# Maker_Faire_Machine_Panel3.net
KiCad netlist of a schematic drawn in EAGLE
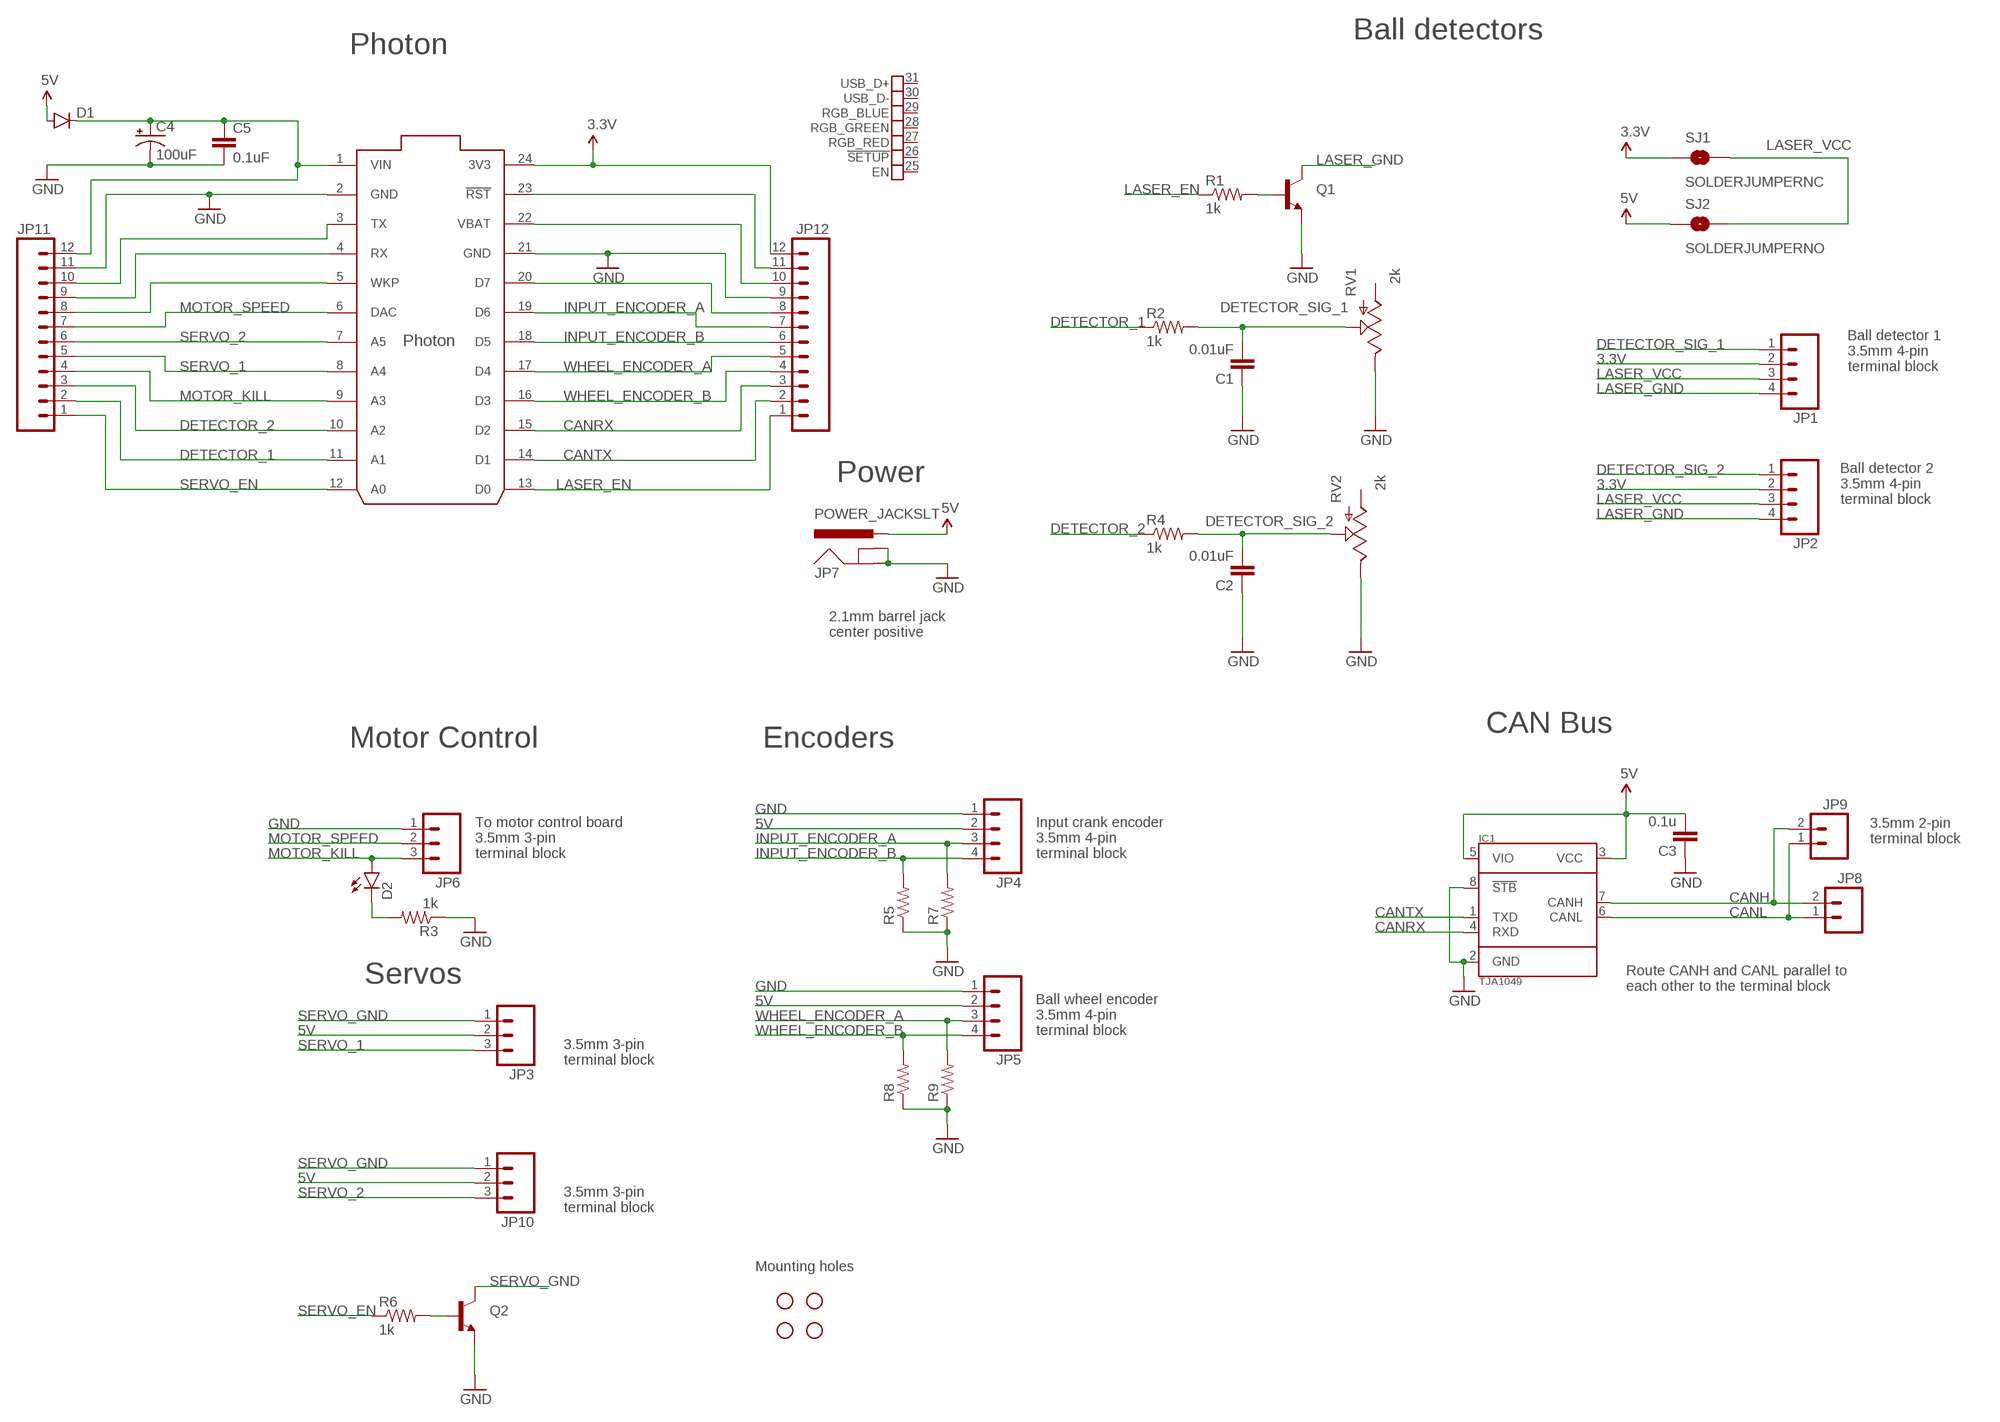
[diagram p0: schematic, sheet 1]

(export (version "E")
  (design (tool "Eeschema 10.0.6"))
  (components
    (comp (ref "C1")
      (value "0.01uF")
      (footprint "eagle-import:1206")
      (fields (field (name "PARTNO") "12065C103KAT2A"))
      (libsource (lib "eagle-import") (part "SparkFun-Passives_CAP1206"))
    )
    (comp (ref "C2")
      (value "0.01uF")
      (footprint "eagle-import:1206")
      (fields (field (name "PARTNO") "12065C103KAT2A"))
      (libsource (lib "eagle-import") (part "SparkFun-Passives_CAP1206"))
    )
    (comp (ref "C3")
      (value "0.1u")
      (footprint "eagle-import:1206")
      (fields (field (name "PARTNO") "12065C104KAT2A"))
      (libsource (lib "eagle-import") (part "CAP1206"))
    )
    (comp (ref "C4")
      (value "100uF")
      (footprint "eagle-import:CPOL-RADIAL-100UF-25V")
      (fields (field (name "PARTNO") "EEU-FM1H101B"))
      (libsource (lib "eagle-import") (part "CAP_POLPTH1"))
    )
    (comp (ref "C5")
      (value "0.1uF")
      (footprint "eagle-import:1206")
      (fields (field (name "PARTNO") "12065C104KAT2A"))
      (libsource (lib "eagle-import") (part "CAP1206"))
    )
    (comp (ref "D1")
      (value "DIODESMA")
      (footprint "eagle-import:SMA-DIODE")
      (fields (field (name "PARTNO") "B230A-13-F"))
      (libsource (lib "eagle-import") (part "DIODESMA"))
    )
    (comp (ref "D2")
      (value "LED5MM")
      (footprint "eagle-import:LED5MM")
      (fields (field (name "PARTNO") "SSL-LX5093HD"))
      (libsource (lib "eagle-import") (part "LED5MM"))
    )
    (comp (ref "IC1")
      (value "TJA1049")
      (footprint "eagle-import:SO8")
      (fields (field (name "PARTNO") "TJA1049T-118"))
      (libsource (lib "eagle-import") (part "TJA1049"))
    )
    (comp (ref "JP1")
      (value "M04SCREW")
      (footprint "eagle-import:SCREWTERMINAL-3.5MM-4")
      (fields (field (name "PARTNO") "OSTTE040104"))
      (libsource (lib "eagle-import") (part "M04SCREW"))
    )
    (comp (ref "JP2")
      (value "M04SCREW")
      (footprint "eagle-import:SCREWTERMINAL-3.5MM-4")
      (fields (field (name "PARTNO") "OSTTE040104"))
      (libsource (lib "eagle-import") (part "M04SCREW"))
    )
    (comp (ref "JP3")
      (value "M03SCREW")
      (footprint "eagle-import:SCREWTERMINAL-3.5MM-3")
      (fields (field (name "PARTNO") "OSTTE020104"))
      (libsource (lib "eagle-import") (part "M03SCREW"))
    )
    (comp (ref "JP4")
      (value "M04SCREW")
      (footprint "eagle-import:SCREWTERMINAL-3.5MM-4")
      (fields (field (name "PARTNO") "OSTTE040104"))
      (libsource (lib "eagle-import") (part "M04SCREW"))
    )
    (comp (ref "JP5")
      (value "M04SCREW")
      (footprint "eagle-import:SCREWTERMINAL-3.5MM-4")
      (fields (field (name "PARTNO") "OSTTE030104"))
      (libsource (lib "eagle-import") (part "M04SCREW"))
    )
    (comp (ref "JP6")
      (value "M03SCREW")
      (footprint "eagle-import:SCREWTERMINAL-3.5MM-3")
      (fields (field (name "PARTNO") "OSTTE020104"))
      (libsource (lib "eagle-import") (part "M03SCREW"))
    )
    (comp (ref "JP7")
      (value "POWER_JACKSLT")
      (footprint "eagle-import:POWER_JACK_SLOT")
      (fields (field (name "PARTNO") "PJ-202A"))
      (libsource (lib "eagle-import") (part "POWER_JACKSLT"))
    )
    (comp (ref "JP8")
      (value "M023.5MM")
      (footprint "eagle-import:SCREWTERMINAL-3.5MM-2")
      (fields (field (name "PARTNO") "OSTTE020104"))
      (libsource (lib "eagle-import") (part "M023.5MM"))
    )
    (comp (ref "JP9")
      (value "M023.5MM")
      (footprint "eagle-import:SCREWTERMINAL-3.5MM-2")
      (fields (field (name "PARTNO") "OSTTE020104"))
      (libsource (lib "eagle-import") (part "M023.5MM"))
    )
    (comp (ref "JP10")
      (value "M03SCREW")
      (footprint "eagle-import:SCREWTERMINAL-3.5MM-3")
      (fields (field (name "PARTNO") "OSTTE030104"))
      (libsource (lib "eagle-import") (part "M03SCREW"))
    )
    (comp (ref "JP11")
      (value "M12NO_SILK")
      (footprint "eagle-import:1X12_NO_SILK")
      (libsource (lib "eagle-import") (part "M12NO_SILK"))
    )
    (comp (ref "JP12")
      (value "M12NO_SILK")
      (footprint "eagle-import:1X12_NO_SILK")
      (libsource (lib "eagle-import") (part "M12NO_SILK"))
    )
    (comp (ref "Q1")
      (value "TRANSISTOR_NPNTO-92-AMMO")
      (footprint "eagle-import:TO-92-AMMO")
      (fields (field (name "PARTNO") "PN2222ABU"))
      (libsource (lib "eagle-import") (part "TRANSISTOR_NPNTO-92-AMMO"))
    )
    (comp (ref "Q2")
      (value "TRANSISTOR_NPNTO-92-AMMO")
      (footprint "eagle-import:TO-92-AMMO")
      (fields (field (name "PARTNO") "PN2222ABU"))
      (libsource (lib "eagle-import") (part "TRANSISTOR_NPNTO-92-AMMO"))
    )
    (comp (ref "R1")
      (value "1k")
      (footprint "eagle-import:1206")
      (fields (field (name "PARTNO") "ERJ-8ENF1001V"))
      (libsource (lib "eagle-import") (part "RESISTOR1206"))
    )
    (comp (ref "R2")
      (value "1k")
      (footprint "eagle-import:1206")
      (fields (field (name "PARTNO") "ERJ-8ENF1001V"))
      (libsource (lib "eagle-import") (part "RESISTOR1206"))
    )
    (comp (ref "R3")
      (value "1k")
      (footprint "eagle-import:1206")
      (fields (field (name "PARTNO") "ERJ-8ENF1001V"))
      (libsource (lib "eagle-import") (part "RESISTOR1206"))
    )
    (comp (ref "R4")
      (value "1k")
      (footprint "eagle-import:1206")
      (fields (field (name "PARTNO") "ERJ-8ENF1001V"))
      (libsource (lib "eagle-import") (part "RESISTOR1206"))
    )
    (comp (ref "R5")
      (value "RESISTORKIT")
      (footprint "eagle-import:AXIAL-0.3-KIT")
      (libsource (lib "eagle-import") (part "SparkFun-Resistors_RESISTORKIT"))
    )
    (comp (ref "R6")
      (value "1k")
      (footprint "eagle-import:1206")
      (fields (field (name "PARTNO") "ERJ-8ENF1001V"))
      (libsource (lib "eagle-import") (part "RESISTOR1206"))
    )
    (comp (ref "R7")
      (value "RESISTORKIT")
      (footprint "eagle-import:AXIAL-0.3-KIT")
      (libsource (lib "eagle-import") (part "SparkFun-Resistors_RESISTORKIT"))
    )
    (comp (ref "R8")
      (value "RESISTORKIT")
      (footprint "eagle-import:AXIAL-0.3-KIT")
      (libsource (lib "eagle-import") (part "SparkFun-Resistors_RESISTORKIT"))
    )
    (comp (ref "R9")
      (value "RESISTORKIT")
      (footprint "eagle-import:AXIAL-0.3-KIT")
      (libsource (lib "eagle-import") (part "SparkFun-Resistors_RESISTORKIT"))
    )
    (comp (ref "RV1")
      (value "2k")
      (footprint "eagle-import:3362U")
      (fields (field (name "PARTNO") "3362U-1-202LF"))
      (libsource (lib "eagle-import") (part "POT100K_3362U"))
    )
    (comp (ref "RV2")
      (value "2k")
      (footprint "eagle-import:3362U")
      (fields (field (name "PARTNO") "3362U-1-202LF"))
      (libsource (lib "eagle-import") (part "POT100K_3362U"))
    )
    (comp (ref "SJ1")
      (value "SOLDERJUMPERNC")
      (footprint "eagle-import:SJ_2S")
      (libsource (lib "eagle-import") (part "SOLDERJUMPERNC"))
    )
    (comp (ref "SJ2")
      (value "SOLDERJUMPERNO")
      (footprint "eagle-import:SJ_2S-NO")
      (libsource (lib "eagle-import") (part "SOLDERJUMPERNO"))
    )
    (comp (ref "STANDOFF1")
      (value "STAND-OFF")
      (footprint "eagle-import:STAND-OFF")
      (libsource (lib "eagle-import") (part "STAND-OFF"))
    )
    (comp (ref "STANDOFF2")
      (value "STAND-OFF")
      (footprint "eagle-import:STAND-OFF")
      (libsource (lib "eagle-import") (part "STAND-OFF"))
    )
    (comp (ref "STANDOFF3")
      (value "STAND-OFF")
      (footprint "eagle-import:STAND-OFF")
      (libsource (lib "eagle-import") (part "STAND-OFF"))
    )
    (comp (ref "STANDOFF4")
      (value "STAND-OFF")
      (footprint "eagle-import:STAND-OFF")
      (libsource (lib "eagle-import") (part "STAND-OFF"))
    )
    (comp (ref "U$1")
      (value "PHOTON_SMD")
      (footprint "eagle-import:PHOTON_SMD")
      (libsource (lib "eagle-import") (part "PHOTON_SMD"))
    )
  )
  (nets
    (net (code "1") (name "/CANH") (class "Default")
      (node (ref "IC1") (pin "7") (pinfunction "CANH_7") (pintype "bidirectional"))
      (node (ref "JP8") (pin "2") (pinfunction "2_2") (pintype "passive"))
      (node (ref "JP9") (pin "2") (pinfunction "2_2") (pintype "passive"))
    )
    (net (code "2") (name "/CANL") (class "Default")
      (node (ref "IC1") (pin "6") (pinfunction "CANL_6") (pintype "bidirectional"))
      (node (ref "JP8") (pin "1") (pinfunction "1_1") (pintype "passive"))
      (node (ref "JP9") (pin "1") (pinfunction "1_1") (pintype "passive"))
    )
    (net (code "3") (name "/CANRX") (class "Default")
      (node (ref "IC1") (pin "4") (pinfunction "RXD_4") (pintype "bidirectional"))
      (node (ref "JP12") (pin "3") (pinfunction "3_3") (pintype "passive"))
      (node (ref "U$1") (pin "15") (pinfunction "D2_15") (pintype "bidirectional"))
    )
    (net (code "4") (name "/CANTX") (class "Default")
      (node (ref "IC1") (pin "1") (pinfunction "TXD_1") (pintype "bidirectional"))
      (node (ref "JP12") (pin "2") (pinfunction "2_2") (pintype "passive"))
      (node (ref "U$1") (pin "14") (pinfunction "D1_14") (pintype "bidirectional"))
    )
    (net (code "5") (name "/DETECTOR_1") (class "Default")
      (node (ref "JP11") (pin "2") (pinfunction "2_2") (pintype "passive"))
      (node (ref "R2") (pin "1") (pinfunction "1_1") (pintype "passive"))
      (node (ref "U$1") (pin "11") (pinfunction "A1_11") (pintype "bidirectional"))
    )
    (net (code "6") (name "/DETECTOR_2") (class "Default")
      (node (ref "JP11") (pin "3") (pinfunction "3_3") (pintype "passive"))
      (node (ref "R4") (pin "1") (pinfunction "1_1") (pintype "passive"))
      (node (ref "U$1") (pin "10") (pinfunction "A2_10") (pintype "bidirectional"))
    )
    (net (code "7") (name "/DETECTOR_SIG_1") (class "Default")
      (node (ref "C1") (pin "2") (pinfunction "2_2") (pintype "passive"))
      (node (ref "JP1") (pin "1") (pinfunction "1_1") (pintype "passive"))
      (node (ref "R2") (pin "2") (pinfunction "2_2") (pintype "passive"))
      (node (ref "RV1") (pin "P$2") (pinfunction "S_P$2") (pintype "passive"))
    )
    (net (code "8") (name "/DETECTOR_SIG_2") (class "Default")
      (node (ref "C2") (pin "2") (pinfunction "2_2") (pintype "passive"))
      (node (ref "JP2") (pin "1") (pinfunction "1_1") (pintype "passive"))
      (node (ref "R4") (pin "2") (pinfunction "2_2") (pintype "passive"))
      (node (ref "RV2") (pin "P$2") (pinfunction "S_P$2") (pintype "passive"))
    )
    (net (code "9") (name "/INPUT_ENCODER_A") (class "Default")
      (node (ref "JP12") (pin "7") (pinfunction "7_7") (pintype "passive"))
      (node (ref "JP4") (pin "3") (pinfunction "3_3") (pintype "passive"))
      (node (ref "R7") (pin "P$2") (pinfunction "2_P$2") (pintype "passive"))
      (node (ref "U$1") (pin "19") (pinfunction "D6_19") (pintype "bidirectional"))
    )
    (net (code "10") (name "/INPUT_ENCODER_B") (class "Default")
      (node (ref "JP12") (pin "6") (pinfunction "6_6") (pintype "passive"))
      (node (ref "JP4") (pin "4") (pinfunction "4_4") (pintype "passive"))
      (node (ref "R5") (pin "P$2") (pinfunction "2_P$2") (pintype "passive"))
      (node (ref "U$1") (pin "18") (pinfunction "D5_18") (pintype "bidirectional"))
    )
    (net (code "11") (name "/LASER_EN") (class "Default")
      (node (ref "JP12") (pin "1") (pinfunction "1_1") (pintype "passive"))
      (node (ref "R1") (pin "1") (pinfunction "1_1") (pintype "passive"))
      (node (ref "U$1") (pin "13") (pinfunction "D0_13") (pintype "bidirectional"))
    )
    (net (code "12") (name "/LASER_GND") (class "Default")
      (node (ref "JP1") (pin "4") (pinfunction "4_4") (pintype "passive"))
      (node (ref "JP2") (pin "4") (pinfunction "4_4") (pintype "passive"))
      (node (ref "Q1") (pin "3") (pinfunction "C_3") (pintype "passive"))
    )
    (net (code "13") (name "/LASER_VCC") (class "Default")
      (node (ref "JP1") (pin "3") (pinfunction "3_3") (pintype "passive"))
      (node (ref "JP2") (pin "3") (pinfunction "3_3") (pintype "passive"))
      (node (ref "SJ1") (pin "2") (pinfunction "2_2") (pintype "passive"))
      (node (ref "SJ2") (pin "2") (pinfunction "2_2") (pintype "passive"))
    )
    (net (code "14") (name "/MOTOR_KILL") (class "Default")
      (node (ref "D2") (pin "A") (pinfunction "A_A") (pintype "passive"))
      (node (ref "JP11") (pin "4") (pinfunction "4_4") (pintype "passive"))
      (node (ref "JP6") (pin "3") (pinfunction "3_3") (pintype "passive"))
      (node (ref "U$1") (pin "9") (pinfunction "A3_9") (pintype "bidirectional"))
    )
    (net (code "15") (name "/MOTOR_SPEED") (class "Default")
      (node (ref "JP11") (pin "7") (pinfunction "7_7") (pintype "passive"))
      (node (ref "JP6") (pin "2") (pinfunction "2_2") (pintype "passive"))
      (node (ref "U$1") (pin "6") (pinfunction "DAC_6") (pintype "bidirectional"))
    )
    (net (code "16") (name "/SERVO_1") (class "Default")
      (node (ref "JP11") (pin "5") (pinfunction "5_5") (pintype "passive"))
      (node (ref "JP3") (pin "3") (pinfunction "3_3") (pintype "passive"))
      (node (ref "U$1") (pin "8") (pinfunction "A4_8") (pintype "bidirectional"))
    )
    (net (code "17") (name "/SERVO_2") (class "Default")
      (node (ref "JP10") (pin "3") (pinfunction "3_3") (pintype "passive"))
      (node (ref "JP11") (pin "6") (pinfunction "6_6") (pintype "passive"))
      (node (ref "U$1") (pin "7") (pinfunction "A5_7") (pintype "bidirectional"))
    )
    (net (code "18") (name "/SERVO_EN") (class "Default")
      (node (ref "JP11") (pin "1") (pinfunction "1_1") (pintype "passive"))
      (node (ref "R6") (pin "1") (pinfunction "1_1") (pintype "passive"))
      (node (ref "U$1") (pin "12") (pinfunction "A0_12") (pintype "bidirectional"))
    )
    (net (code "19") (name "/SERVO_GND") (class "Default")
      (node (ref "JP10") (pin "1") (pinfunction "1_1") (pintype "passive"))
      (node (ref "JP3") (pin "1") (pinfunction "1_1") (pintype "passive"))
      (node (ref "Q2") (pin "3") (pinfunction "C_3") (pintype "passive"))
    )
    (net (code "20") (name "/WHEEL_ENCODER_A") (class "Default")
      (node (ref "JP12") (pin "5") (pinfunction "5_5") (pintype "passive"))
      (node (ref "JP5") (pin "3") (pinfunction "3_3") (pintype "passive"))
      (node (ref "R9") (pin "P$2") (pinfunction "2_P$2") (pintype "passive"))
      (node (ref "U$1") (pin "17") (pinfunction "D4_17") (pintype "bidirectional"))
    )
    (net (code "21") (name "/WHEEL_ENCODER_B") (class "Default")
      (node (ref "JP12") (pin "4") (pinfunction "4_4") (pintype "passive"))
      (node (ref "JP5") (pin "4") (pinfunction "4_4") (pintype "passive"))
      (node (ref "R8") (pin "P$2") (pinfunction "2_P$2") (pintype "passive"))
      (node (ref "U$1") (pin "16") (pinfunction "D3_16") (pintype "bidirectional"))
    )
    (net (code "22") (name "3.3V") (class "Default")
      (node (ref "JP1") (pin "2") (pinfunction "2_2") (pintype "passive"))
      (node (ref "JP12") (pin "12") (pinfunction "12_12") (pintype "passive"))
      (node (ref "JP2") (pin "2") (pinfunction "2_2") (pintype "passive"))
      (node (ref "SJ1") (pin "1") (pinfunction "1_1") (pintype "passive"))
      (node (ref "U$1") (pin "24") (pinfunction "3V3_24") (pintype "power_in"))
    )
    (net (code "23") (name "5V") (class "Default")
      (node (ref "C3") (pin "2") (pinfunction "2_2") (pintype "passive"))
      (node (ref "D1") (pin "A") (pinfunction "A_A") (pintype "passive"))
      (node (ref "IC1") (pin "3") (pinfunction "VCC_3") (pintype "bidirectional"))
      (node (ref "IC1") (pin "5") (pinfunction "VIO_5") (pintype "bidirectional"))
      (node (ref "JP10") (pin "2") (pinfunction "2_2") (pintype "passive"))
      (node (ref "JP3") (pin "2") (pinfunction "2_2") (pintype "passive"))
      (node (ref "JP4") (pin "2") (pinfunction "2_2") (pintype "passive"))
      (node (ref "JP5") (pin "2") (pinfunction "2_2") (pintype "passive"))
      (node (ref "JP7") (pin "PWR") (pinfunction "PWR_PWR") (pintype "bidirectional"))
      (node (ref "SJ2") (pin "1") (pinfunction "1_1") (pintype "passive"))
    )
    (net (code "24") (name "GND") (class "Default")
      (node (ref "C1") (pin "1") (pinfunction "1_1") (pintype "passive"))
      (node (ref "C2") (pin "1") (pinfunction "1_1") (pintype "passive"))
      (node (ref "C3") (pin "1") (pinfunction "1_1") (pintype "passive"))
      (node (ref "C4") (pin "2") (pinfunction "-_2") (pintype "passive"))
      (node (ref "C5") (pin "2") (pinfunction "2_2") (pintype "passive"))
      (node (ref "IC1") (pin "2") (pinfunction "GND_2") (pintype "bidirectional"))
      (node (ref "IC1") (pin "8") (pinfunction "~{STB}_8") (pintype "bidirectional"))
      (node (ref "JP11") (pin "11") (pinfunction "11_11") (pintype "passive"))
      (node (ref "JP12") (pin "9") (pinfunction "9_9") (pintype "passive"))
      (node (ref "JP4") (pin "1") (pinfunction "1_1") (pintype "passive"))
      (node (ref "JP5") (pin "1") (pinfunction "1_1") (pintype "passive"))
      (node (ref "JP6") (pin "1") (pinfunction "1_1") (pintype "passive"))
      (node (ref "JP7") (pin "GND@1") (pinfunction "GNDBREAK_GND@1") (pintype "bidirectional"))
      (node (ref "JP7") (pin "GND@2") (pinfunction "GND_GND@2") (pintype "bidirectional"))
      (node (ref "Q1") (pin "1") (pinfunction "E_1") (pintype "passive"))
      (node (ref "Q2") (pin "1") (pinfunction "E_1") (pintype "passive"))
      (node (ref "R3") (pin "1") (pinfunction "1_1") (pintype "passive"))
      (node (ref "R5") (pin "P$1") (pinfunction "1_P$1") (pintype "passive"))
      (node (ref "R7") (pin "P$1") (pinfunction "1_P$1") (pintype "passive"))
      (node (ref "R8") (pin "P$1") (pinfunction "1_P$1") (pintype "passive"))
      (node (ref "R9") (pin "P$1") (pinfunction "1_P$1") (pintype "passive"))
      (node (ref "RV1") (pin "P$1") (pinfunction "E_P$1") (pintype "passive"))
      (node (ref "RV2") (pin "P$1") (pinfunction "E_P$1") (pintype "passive"))
      (node (ref "U$1") (pin "2") (pinfunction "GND_2") (pintype "power_in"))
      (node (ref "U$1") (pin "21") (pinfunction "GND_21") (pintype "power_in"))
    )
    (net (code "25") (name "Net-(C4-+)") (class "Default")
      (node (ref "C4") (pin "1") (pinfunction "+_1") (pintype "passive"))
      (node (ref "C5") (pin "1") (pinfunction "1_1") (pintype "passive"))
      (node (ref "D1") (pin "C") (pinfunction "C_C") (pintype "passive"))
      (node (ref "JP11") (pin "12") (pinfunction "12_12") (pintype "passive"))
      (node (ref "U$1") (pin "1") (pinfunction "VIN_1") (pintype "power_in"))
    )
    (net (code "26") (name "Net-(D2-C)") (class "Default")
      (node (ref "D2") (pin "K") (pinfunction "C_K") (pintype "passive"))
      (node (ref "R3") (pin "2") (pinfunction "2_2") (pintype "passive"))
    )
    (net (code "27") (name "Net-(Q1-B)") (class "Default")
      (node (ref "Q1") (pin "2") (pinfunction "B_2") (pintype "passive"))
      (node (ref "R1") (pin "2") (pinfunction "2_2") (pintype "passive"))
    )
    (net (code "28") (name "Net-(Q2-B)") (class "Default")
      (node (ref "Q2") (pin "2") (pinfunction "B_2") (pintype "passive"))
      (node (ref "R6") (pin "2") (pinfunction "2_2") (pintype "passive"))
    )
    (net (code "29") (name "Net-(U$1A-D7)") (class "Default")
      (node (ref "JP12") (pin "8") (pinfunction "8_8") (pintype "passive"))
      (node (ref "U$1") (pin "20") (pinfunction "D7_20") (pintype "bidirectional"))
    )
    (net (code "30") (name "Net-(U$1A-RX)") (class "Default")
      (node (ref "JP11") (pin "9") (pinfunction "9_9") (pintype "passive"))
      (node (ref "U$1") (pin "4") (pinfunction "RX_4") (pintype "bidirectional"))
    )
    (net (code "31") (name "Net-(U$1A-TX)") (class "Default")
      (node (ref "JP11") (pin "10") (pinfunction "10_10") (pintype "passive"))
      (node (ref "U$1") (pin "3") (pinfunction "TX_3") (pintype "bidirectional"))
    )
    (net (code "32") (name "Net-(U$1A-VBAT)") (class "Default")
      (node (ref "JP12") (pin "10") (pinfunction "10_10") (pintype "passive"))
      (node (ref "U$1") (pin "22") (pinfunction "VBAT_22") (pintype "power_in"))
    )
    (net (code "33") (name "Net-(U$1A-WKP)") (class "Default")
      (node (ref "JP11") (pin "8") (pinfunction "8_8") (pintype "passive"))
      (node (ref "U$1") (pin "5") (pinfunction "WKP_5") (pintype "bidirectional"))
    )
    (net (code "34") (name "Net-(U$1A-~{RST})") (class "Default")
      (node (ref "JP12") (pin "11") (pinfunction "11_11") (pintype "passive"))
      (node (ref "U$1") (pin "23") (pinfunction "~{RST}_23") (pintype "bidirectional"))
    )
    (net (code "35") (name "unconnected-(RV1-A-PadP$3)") (class "Default")
      (node (ref "RV1") (pin "P$3") (pinfunction "A_P$3") (pintype "passive"))
    )
    (net (code "36") (name "unconnected-(RV2-A-PadP$3)") (class "Default")
      (node (ref "RV2") (pin "P$3") (pinfunction "A_P$3") (pintype "passive"))
    )
    (net (code "37") (name "unconnected-(U$1B-EN-Pad25)") (class "Default")
      (node (ref "U$1") (pin "25") (pinfunction "EN_25") (pintype "bidirectional"))
    )
    (net (code "38") (name "unconnected-(U$1B-RGB_BLUE-Pad29)") (class "Default")
      (node (ref "U$1") (pin "29") (pinfunction "RGB_BLUE_29") (pintype "bidirectional"))
    )
    (net (code "39") (name "unconnected-(U$1B-RGB_GREEN-Pad28)") (class "Default")
      (node (ref "U$1") (pin "28") (pinfunction "RGB_GREEN_28") (pintype "bidirectional"))
    )
    (net (code "40") (name "unconnected-(U$1B-RGB_RED-Pad27)") (class "Default")
      (node (ref "U$1") (pin "27") (pinfunction "RGB_RED_27") (pintype "bidirectional"))
    )
    (net (code "41") (name "unconnected-(U$1B-USB_D+-Pad31)") (class "Default")
      (node (ref "U$1") (pin "31") (pinfunction "USB_D+_31") (pintype "bidirectional"))
    )
    (net (code "42") (name "unconnected-(U$1B-USB_D--Pad30)") (class "Default")
      (node (ref "U$1") (pin "30") (pinfunction "USB_D-_30") (pintype "bidirectional"))
    )
    (net (code "43") (name "unconnected-(U$1B-~{SETUP}-Pad26)") (class "Default")
      (node (ref "U$1") (pin "26") (pinfunction "~{SETUP}_26") (pintype "bidirectional"))
    )
  )
)
